# MAX232.net
KiCad netlist of a schematic drawn in Altium Designer
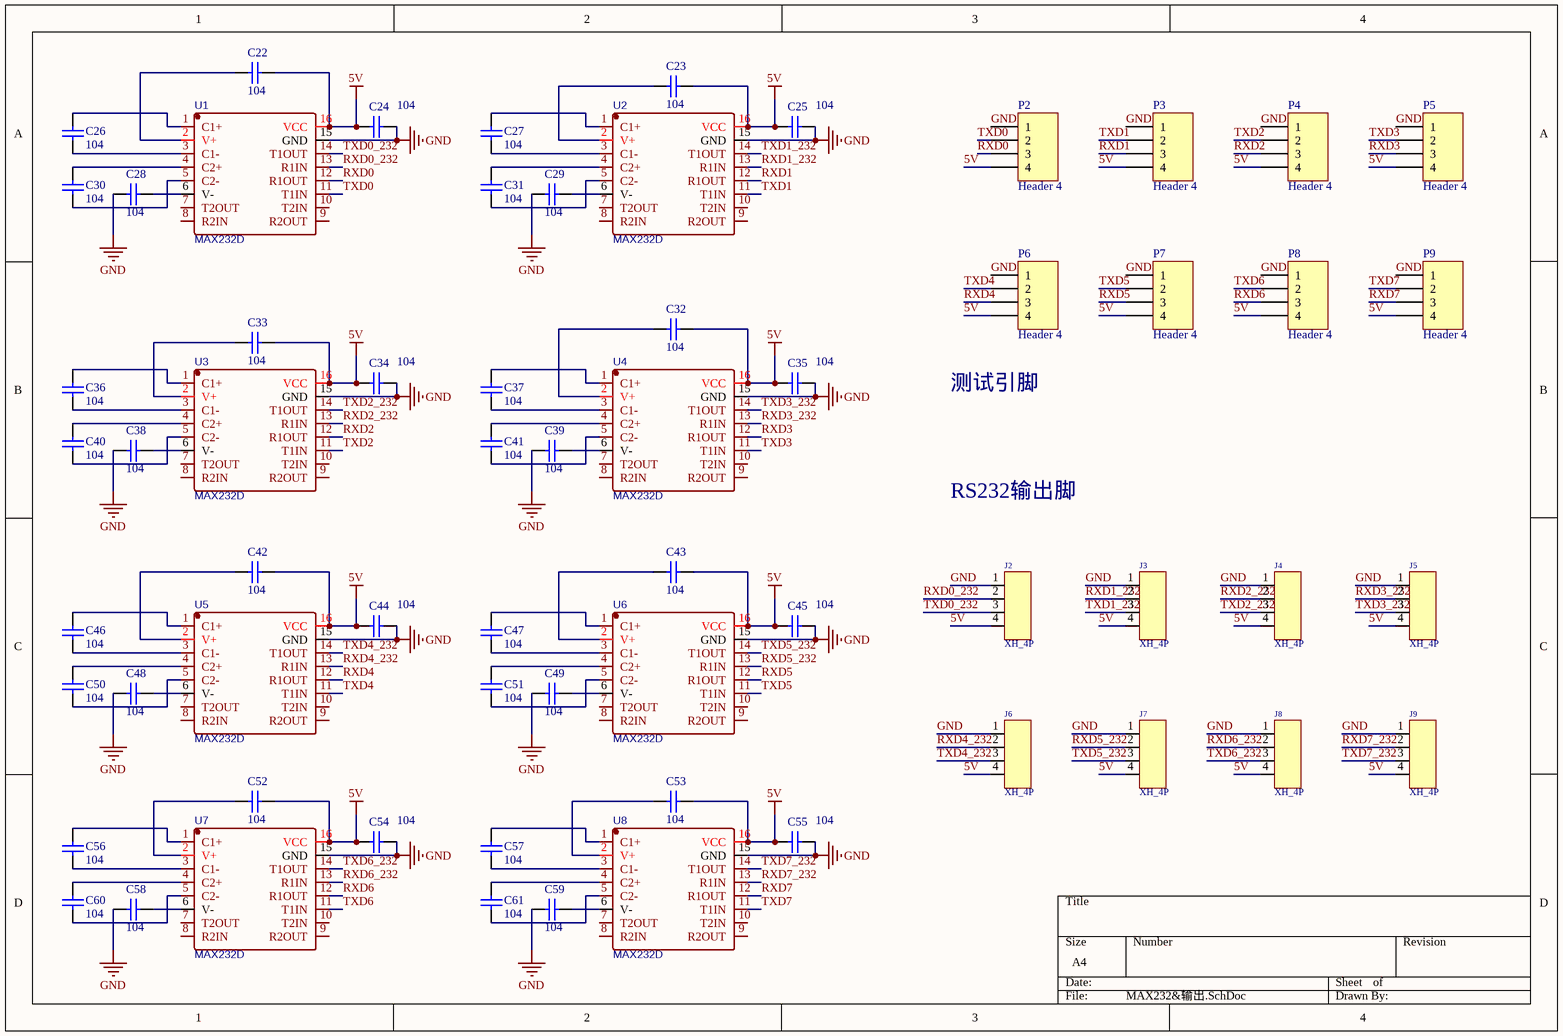
[diagram p0: MAX232&输出.SchDoc]

(export (version "E")
  (design (tool "Eeschema 10.0.6"))
  (components
    (comp (ref "C22")
      (value "104")
      (footprint "0603_C")
      (description "贴片电容")
      (libsource (lib "Miscellaneous Devices LC") (part "0603 100nF (104) 10% 50V"))
    )
    (comp (ref "C23")
      (value "104")
      (footprint "0603_C")
      (description "贴片电容")
      (libsource (lib "Miscellaneous Devices LC") (part "0603 100nF (104) 10% 50V"))
    )
    (comp (ref "C24")
      (value "104")
      (footprint "0603_C")
      (description "贴片电容")
      (libsource (lib "Miscellaneous Devices LC") (part "0603 100nF (104) 10% 50V"))
    )
    (comp (ref "C25")
      (value "104")
      (footprint "0603_C")
      (description "贴片电容")
      (libsource (lib "Miscellaneous Devices LC") (part "0603 100nF (104) 10% 50V"))
    )
    (comp (ref "C26")
      (value "104")
      (footprint "0603_C")
      (description "贴片电容")
      (libsource (lib "Miscellaneous Devices LC") (part "0603 100nF (104) 10% 50V"))
    )
    (comp (ref "C27")
      (value "104")
      (footprint "0603_C")
      (description "贴片电容")
      (libsource (lib "Miscellaneous Devices LC") (part "0603 100nF (104) 10% 50V"))
    )
    (comp (ref "C28")
      (value "104")
      (footprint "0603_C")
      (description "贴片电容")
      (libsource (lib "Miscellaneous Devices LC") (part "0603 100nF (104) 10% 50V"))
    )
    (comp (ref "C29")
      (value "104")
      (footprint "0603_C")
      (description "贴片电容")
      (libsource (lib "Miscellaneous Devices LC") (part "0603 100nF (104) 10% 50V"))
    )
    (comp (ref "C30")
      (value "104")
      (footprint "0603_C")
      (description "贴片电容")
      (libsource (lib "Miscellaneous Devices LC") (part "0603 100nF (104) 10% 50V"))
    )
    (comp (ref "C31")
      (value "104")
      (footprint "0603_C")
      (description "贴片电容")
      (libsource (lib "Miscellaneous Devices LC") (part "0603 100nF (104) 10% 50V"))
    )
    (comp (ref "C32")
      (value "104")
      (footprint "0603_C")
      (description "贴片电容")
      (libsource (lib "Miscellaneous Devices LC") (part "0603 100nF (104) 10% 50V"))
    )
    (comp (ref "C33")
      (value "104")
      (footprint "0603_C")
      (description "贴片电容")
      (libsource (lib "Miscellaneous Devices LC") (part "0603 100nF (104) 10% 50V"))
    )
    (comp (ref "C34")
      (value "104")
      (footprint "0603_C")
      (description "贴片电容")
      (libsource (lib "Miscellaneous Devices LC") (part "0603 100nF (104) 10% 50V"))
    )
    (comp (ref "C35")
      (value "104")
      (footprint "0603_C")
      (description "贴片电容")
      (libsource (lib "Miscellaneous Devices LC") (part "0603 100nF (104) 10% 50V"))
    )
    (comp (ref "C36")
      (value "104")
      (footprint "0603_C")
      (description "贴片电容")
      (libsource (lib "Miscellaneous Devices LC") (part "0603 100nF (104) 10% 50V"))
    )
    (comp (ref "C37")
      (value "104")
      (footprint "0603_C")
      (description "贴片电容")
      (libsource (lib "Miscellaneous Devices LC") (part "0603 100nF (104) 10% 50V"))
    )
    (comp (ref "C38")
      (value "104")
      (footprint "0603_C")
      (description "贴片电容")
      (libsource (lib "Miscellaneous Devices LC") (part "0603 100nF (104) 10% 50V"))
    )
    (comp (ref "C39")
      (value "104")
      (footprint "0603_C")
      (description "贴片电容")
      (libsource (lib "Miscellaneous Devices LC") (part "0603 100nF (104) 10% 50V"))
    )
    (comp (ref "C40")
      (value "104")
      (footprint "0603_C")
      (description "贴片电容")
      (libsource (lib "Miscellaneous Devices LC") (part "0603 100nF (104) 10% 50V"))
    )
    (comp (ref "C41")
      (value "104")
      (footprint "0603_C")
      (description "贴片电容")
      (libsource (lib "Miscellaneous Devices LC") (part "0603 100nF (104) 10% 50V"))
    )
    (comp (ref "C42")
      (value "104")
      (footprint "0603_C")
      (description "贴片电容")
      (libsource (lib "Miscellaneous Devices LC") (part "0603 100nF (104) 10% 50V"))
    )
    (comp (ref "C43")
      (value "104")
      (footprint "0603_C")
      (description "贴片电容")
      (libsource (lib "Miscellaneous Devices LC") (part "0603 100nF (104) 10% 50V"))
    )
    (comp (ref "C44")
      (value "104")
      (footprint "0603_C")
      (description "贴片电容")
      (libsource (lib "Miscellaneous Devices LC") (part "0603 100nF (104) 10% 50V"))
    )
    (comp (ref "C45")
      (value "104")
      (footprint "0603_C")
      (description "贴片电容")
      (libsource (lib "Miscellaneous Devices LC") (part "0603 100nF (104) 10% 50V"))
    )
    (comp (ref "C46")
      (value "104")
      (footprint "0603_C")
      (description "贴片电容")
      (libsource (lib "Miscellaneous Devices LC") (part "0603 100nF (104) 10% 50V"))
    )
    (comp (ref "C47")
      (value "104")
      (footprint "0603_C")
      (description "贴片电容")
      (libsource (lib "Miscellaneous Devices LC") (part "0603 100nF (104) 10% 50V"))
    )
    (comp (ref "C48")
      (value "104")
      (footprint "0603_C")
      (description "贴片电容")
      (libsource (lib "Miscellaneous Devices LC") (part "0603 100nF (104) 10% 50V"))
    )
    (comp (ref "C49")
      (value "104")
      (footprint "0603_C")
      (description "贴片电容")
      (libsource (lib "Miscellaneous Devices LC") (part "0603 100nF (104) 10% 50V"))
    )
    (comp (ref "C50")
      (value "104")
      (footprint "0603_C")
      (description "贴片电容")
      (libsource (lib "Miscellaneous Devices LC") (part "0603 100nF (104) 10% 50V"))
    )
    (comp (ref "C51")
      (value "104")
      (footprint "0603_C")
      (description "贴片电容")
      (libsource (lib "Miscellaneous Devices LC") (part "0603 100nF (104) 10% 50V"))
    )
    (comp (ref "C52")
      (value "104")
      (footprint "0603_C")
      (description "贴片电容")
      (libsource (lib "Miscellaneous Devices LC") (part "0603 100nF (104) 10% 50V"))
    )
    (comp (ref "C53")
      (value "104")
      (footprint "0603_C")
      (description "贴片电容")
      (libsource (lib "Miscellaneous Devices LC") (part "0603 100nF (104) 10% 50V"))
    )
    (comp (ref "C54")
      (value "104")
      (footprint "0603_C")
      (description "贴片电容")
      (libsource (lib "Miscellaneous Devices LC") (part "0603 100nF (104) 10% 50V"))
    )
    (comp (ref "C55")
      (value "104")
      (footprint "0603_C")
      (description "贴片电容")
      (libsource (lib "Miscellaneous Devices LC") (part "0603 100nF (104) 10% 50V"))
    )
    (comp (ref "C56")
      (value "104")
      (footprint "0603_C")
      (description "贴片电容")
      (libsource (lib "Miscellaneous Devices LC") (part "0603 100nF (104) 10% 50V"))
    )
    (comp (ref "C57")
      (value "104")
      (footprint "0603_C")
      (description "贴片电容")
      (libsource (lib "Miscellaneous Devices LC") (part "0603 100nF (104) 10% 50V"))
    )
    (comp (ref "C58")
      (value "104")
      (footprint "0603_C")
      (description "贴片电容")
      (libsource (lib "Miscellaneous Devices LC") (part "0603 100nF (104) 10% 50V"))
    )
    (comp (ref "C59")
      (value "104")
      (footprint "0603_C")
      (description "贴片电容")
      (libsource (lib "Miscellaneous Devices LC") (part "0603 100nF (104) 10% 50V"))
    )
    (comp (ref "C60")
      (value "104")
      (footprint "0603_C")
      (description "贴片电容")
      (libsource (lib "Miscellaneous Devices LC") (part "0603 100nF (104) 10% 50V"))
    )
    (comp (ref "C61")
      (value "104")
      (footprint "0603_C")
      (description "贴片电容")
      (libsource (lib "Miscellaneous Devices LC") (part "0603 100nF (104) 10% 50V"))
    )
    (comp (ref "J2") (value "XH_4P") (footprint "XH_4P直插弯针") (libsource (lib "XH_Connectors") (part "XH_4P")))
    (comp (ref "J3") (value "XH_4P") (footprint "XH_4P直插弯针") (libsource (lib "XH_Connectors") (part "XH_4P")))
    (comp (ref "J4") (value "XH_4P") (footprint "XH_4P直插弯针") (libsource (lib "XH_Connectors") (part "XH_4P")))
    (comp (ref "J5") (value "XH_4P") (footprint "XH_4P直插弯针") (libsource (lib "XH_Connectors") (part "XH_4P")))
    (comp (ref "J6") (value "XH_4P") (footprint "XH_4P直插弯针") (libsource (lib "XH_Connectors") (part "XH_4P")))
    (comp (ref "J7") (value "XH_4P") (footprint "XH_4P直插弯针") (libsource (lib "XH_Connectors") (part "XH_4P")))
    (comp (ref "J8") (value "XH_4P") (footprint "XH_4P直插弯针") (libsource (lib "XH_Connectors") (part "XH_4P")))
    (comp (ref "J9") (value "XH_4P") (footprint "XH_4P直插弯针") (libsource (lib "XH_Connectors") (part "XH_4P")))
    (comp (ref "P2")
      (value "Header 4")
      (footprint "HDR1X4")
      (description "Header, 4-Pin")
      (fields (field (name "PUBLISHER") "Altium Limited"))
      (libsource (lib "Miscellaneous Connectors") (part "Header 4"))
    )
    (comp (ref "P3")
      (value "Header 4")
      (footprint "HDR1X4")
      (description "Header, 4-Pin")
      (fields (field (name "PUBLISHER") "Altium Limited"))
      (libsource (lib "Miscellaneous Connectors") (part "Header 4"))
    )
    (comp (ref "P4")
      (value "Header 4")
      (footprint "HDR1X4")
      (description "Header, 4-Pin")
      (fields (field (name "PUBLISHER") "Altium Limited"))
      (libsource (lib "Miscellaneous Connectors") (part "Header 4"))
    )
    (comp (ref "P5")
      (value "Header 4")
      (footprint "HDR1X4")
      (description "Header, 4-Pin")
      (fields (field (name "PUBLISHER") "Altium Limited"))
      (libsource (lib "Miscellaneous Connectors") (part "Header 4"))
    )
    (comp (ref "P6")
      (value "Header 4")
      (footprint "HDR1X4")
      (description "Header, 4-Pin")
      (fields (field (name "PUBLISHER") "Altium Limited"))
      (libsource (lib "Miscellaneous Connectors") (part "Header 4"))
    )
    (comp (ref "P7")
      (value "Header 4")
      (footprint "HDR1X4")
      (description "Header, 4-Pin")
      (fields (field (name "PUBLISHER") "Altium Limited"))
      (libsource (lib "Miscellaneous Connectors") (part "Header 4"))
    )
    (comp (ref "P8")
      (value "Header 4")
      (footprint "HDR1X4")
      (description "Header, 4-Pin")
      (fields (field (name "PUBLISHER") "Altium Limited"))
      (libsource (lib "Miscellaneous Connectors") (part "Header 4"))
    )
    (comp (ref "P9")
      (value "Header 4")
      (footprint "HDR1X4")
      (description "Header, 4-Pin")
      (fields (field (name "PUBLISHER") "Altium Limited"))
      (libsource (lib "Miscellaneous Connectors") (part "Header 4"))
    )
    (comp (ref "U1")
      (value "MAX232D")
      (footprint "SOIC-16_L9.9-W3.9-P1.27-LS6.0-BL")
      (fields (field (name "BOM_SUPPLIER PART") "C350552") (field (name "CONTRIBUTOR") "LCSC"))
      (libsource (lib "Integrated_Library") (part "MAX232D"))
    )
    (comp (ref "U2")
      (value "MAX232D")
      (footprint "SOIC-16_L9.9-W3.9-P1.27-LS6.0-BL")
      (fields (field (name "BOM_SUPPLIER PART") "C350552") (field (name "CONTRIBUTOR") "LCSC"))
      (libsource (lib "Integrated_Library") (part "MAX232D"))
    )
    (comp (ref "U3")
      (value "MAX232D")
      (footprint "SOIC-16_L9.9-W3.9-P1.27-LS6.0-BL")
      (fields (field (name "BOM_SUPPLIER PART") "C350552") (field (name "CONTRIBUTOR") "LCSC"))
      (libsource (lib "Integrated_Library") (part "MAX232D"))
    )
    (comp (ref "U4")
      (value "MAX232D")
      (footprint "SOIC-16_L9.9-W3.9-P1.27-LS6.0-BL")
      (fields (field (name "BOM_SUPPLIER PART") "C350552") (field (name "CONTRIBUTOR") "LCSC"))
      (libsource (lib "Integrated_Library") (part "MAX232D"))
    )
    (comp (ref "U5")
      (value "MAX232D")
      (footprint "SOIC-16_L9.9-W3.9-P1.27-LS6.0-BL")
      (fields (field (name "BOM_SUPPLIER PART") "C350552") (field (name "CONTRIBUTOR") "LCSC"))
      (libsource (lib "Integrated_Library") (part "MAX232D"))
    )
    (comp (ref "U6")
      (value "MAX232D")
      (footprint "SOIC-16_L9.9-W3.9-P1.27-LS6.0-BL")
      (fields (field (name "BOM_SUPPLIER PART") "C350552") (field (name "CONTRIBUTOR") "LCSC"))
      (libsource (lib "Integrated_Library") (part "MAX232D"))
    )
    (comp (ref "U7")
      (value "MAX232D")
      (footprint "SOIC-16_L9.9-W3.9-P1.27-LS6.0-BL")
      (fields (field (name "BOM_SUPPLIER PART") "C350552") (field (name "CONTRIBUTOR") "LCSC"))
      (libsource (lib "Integrated_Library") (part "MAX232D"))
    )
    (comp (ref "U8")
      (value "MAX232D")
      (footprint "SOIC-16_L9.9-W3.9-P1.27-LS6.0-BL")
      (fields (field (name "BOM_SUPPLIER PART") "C350552") (field (name "CONTRIBUTOR") "LCSC"))
      (libsource (lib "Integrated_Library") (part "MAX232D"))
    )
  )
  (nets
    (net (code "1") (name "/RXD0") (class "Default")
      (node (ref "P2") (pin "3") (pinfunction "3_3") (pintype "passive"))
      (node (ref "U1") (pin "12") (pinfunction "R1OUT_12") (pintype "passive"))
    )
    (net (code "2") (name "/RXD0_232") (class "Default")
      (node (ref "J2") (pin "2") (pinfunction "2_2") (pintype "passive"))
      (node (ref "U1") (pin "13") (pinfunction "R1IN_13") (pintype "passive"))
    )
    (net (code "3") (name "/RXD1") (class "Default")
      (node (ref "P3") (pin "3") (pinfunction "3_3") (pintype "passive"))
      (node (ref "U2") (pin "12") (pinfunction "R1OUT_12") (pintype "passive"))
    )
    (net (code "4") (name "/RXD1_232") (class "Default")
      (node (ref "J3") (pin "2") (pinfunction "2_2") (pintype "passive"))
      (node (ref "U2") (pin "13") (pinfunction "R1IN_13") (pintype "passive"))
    )
    (net (code "5") (name "/RXD2") (class "Default")
      (node (ref "P4") (pin "3") (pinfunction "3_3") (pintype "passive"))
      (node (ref "U3") (pin "12") (pinfunction "R1OUT_12") (pintype "passive"))
    )
    (net (code "6") (name "/RXD2_232") (class "Default")
      (node (ref "J4") (pin "2") (pinfunction "2_2") (pintype "passive"))
      (node (ref "U3") (pin "13") (pinfunction "R1IN_13") (pintype "passive"))
    )
    (net (code "7") (name "/RXD3") (class "Default")
      (node (ref "P5") (pin "3") (pinfunction "3_3") (pintype "passive"))
      (node (ref "U4") (pin "12") (pinfunction "R1OUT_12") (pintype "passive"))
    )
    (net (code "8") (name "/RXD3_232") (class "Default")
      (node (ref "J5") (pin "2") (pinfunction "2_2") (pintype "passive"))
      (node (ref "U4") (pin "13") (pinfunction "R1IN_13") (pintype "passive"))
    )
    (net (code "9") (name "/RXD4") (class "Default")
      (node (ref "P6") (pin "3") (pinfunction "3_3") (pintype "passive"))
      (node (ref "U5") (pin "12") (pinfunction "R1OUT_12") (pintype "passive"))
    )
    (net (code "10") (name "/RXD4_232") (class "Default")
      (node (ref "J6") (pin "2") (pinfunction "2_2") (pintype "passive"))
      (node (ref "U5") (pin "13") (pinfunction "R1IN_13") (pintype "passive"))
    )
    (net (code "11") (name "/RXD5") (class "Default")
      (node (ref "P7") (pin "3") (pinfunction "3_3") (pintype "passive"))
      (node (ref "U6") (pin "12") (pinfunction "R1OUT_12") (pintype "passive"))
    )
    (net (code "12") (name "/RXD5_232") (class "Default")
      (node (ref "J7") (pin "2") (pinfunction "2_2") (pintype "passive"))
      (node (ref "U6") (pin "13") (pinfunction "R1IN_13") (pintype "passive"))
    )
    (net (code "13") (name "/RXD6") (class "Default")
      (node (ref "P8") (pin "3") (pinfunction "3_3") (pintype "passive"))
      (node (ref "U7") (pin "12") (pinfunction "R1OUT_12") (pintype "passive"))
    )
    (net (code "14") (name "/RXD6_232") (class "Default")
      (node (ref "J8") (pin "2") (pinfunction "2_2") (pintype "passive"))
      (node (ref "U7") (pin "13") (pinfunction "R1IN_13") (pintype "passive"))
    )
    (net (code "15") (name "/RXD7") (class "Default")
      (node (ref "P9") (pin "3") (pinfunction "3_3") (pintype "passive"))
      (node (ref "U8") (pin "12") (pinfunction "R1OUT_12") (pintype "passive"))
    )
    (net (code "16") (name "/RXD7_232") (class "Default")
      (node (ref "J9") (pin "2") (pinfunction "2_2") (pintype "passive"))
      (node (ref "U8") (pin "13") (pinfunction "R1IN_13") (pintype "passive"))
    )
    (net (code "17") (name "/TXD0") (class "Default")
      (node (ref "P2") (pin "2") (pinfunction "2_2") (pintype "passive"))
      (node (ref "U1") (pin "11") (pinfunction "T1IN_11") (pintype "passive"))
    )
    (net (code "18") (name "/TXD0_232") (class "Default")
      (node (ref "J2") (pin "3") (pinfunction "3_3") (pintype "passive"))
      (node (ref "U1") (pin "14") (pinfunction "T1OUT_14") (pintype "passive"))
    )
    (net (code "19") (name "/TXD1") (class "Default")
      (node (ref "P3") (pin "2") (pinfunction "2_2") (pintype "passive"))
      (node (ref "U2") (pin "11") (pinfunction "T1IN_11") (pintype "passive"))
    )
    (net (code "20") (name "/TXD1_232") (class "Default")
      (node (ref "J3") (pin "3") (pinfunction "3_3") (pintype "passive"))
      (node (ref "U2") (pin "14") (pinfunction "T1OUT_14") (pintype "passive"))
    )
    (net (code "21") (name "/TXD2") (class "Default")
      (node (ref "P4") (pin "2") (pinfunction "2_2") (pintype "passive"))
      (node (ref "U3") (pin "11") (pinfunction "T1IN_11") (pintype "passive"))
    )
    (net (code "22") (name "/TXD2_232") (class "Default")
      (node (ref "J4") (pin "3") (pinfunction "3_3") (pintype "passive"))
      (node (ref "U3") (pin "14") (pinfunction "T1OUT_14") (pintype "passive"))
    )
    (net (code "23") (name "/TXD3") (class "Default")
      (node (ref "P5") (pin "2") (pinfunction "2_2") (pintype "passive"))
      (node (ref "U4") (pin "11") (pinfunction "T1IN_11") (pintype "passive"))
    )
    (net (code "24") (name "/TXD3_232") (class "Default")
      (node (ref "J5") (pin "3") (pinfunction "3_3") (pintype "passive"))
      (node (ref "U4") (pin "14") (pinfunction "T1OUT_14") (pintype "passive"))
    )
    (net (code "25") (name "/TXD4") (class "Default")
      (node (ref "P6") (pin "2") (pinfunction "2_2") (pintype "passive"))
      (node (ref "U5") (pin "11") (pinfunction "T1IN_11") (pintype "passive"))
    )
    (net (code "26") (name "/TXD4_232") (class "Default")
      (node (ref "J6") (pin "3") (pinfunction "3_3") (pintype "passive"))
      (node (ref "U5") (pin "14") (pinfunction "T1OUT_14") (pintype "passive"))
    )
    (net (code "27") (name "/TXD5") (class "Default")
      (node (ref "P7") (pin "2") (pinfunction "2_2") (pintype "passive"))
      (node (ref "U6") (pin "11") (pinfunction "T1IN_11") (pintype "passive"))
    )
    (net (code "28") (name "/TXD5_232") (class "Default")
      (node (ref "J7") (pin "3") (pinfunction "3_3") (pintype "passive"))
      (node (ref "U6") (pin "14") (pinfunction "T1OUT_14") (pintype "passive"))
    )
    (net (code "29") (name "/TXD6") (class "Default")
      (node (ref "P8") (pin "2") (pinfunction "2_2") (pintype "passive"))
      (node (ref "U7") (pin "11") (pinfunction "T1IN_11") (pintype "passive"))
    )
    (net (code "30") (name "/TXD6_232") (class "Default")
      (node (ref "J8") (pin "3") (pinfunction "3_3") (pintype "passive"))
      (node (ref "U7") (pin "14") (pinfunction "T1OUT_14") (pintype "passive"))
    )
    (net (code "31") (name "/TXD7") (class "Default")
      (node (ref "P9") (pin "2") (pinfunction "2_2") (pintype "passive"))
      (node (ref "U8") (pin "11") (pinfunction "T1IN_11") (pintype "passive"))
    )
    (net (code "32") (name "/TXD7_232") (class "Default")
      (node (ref "J9") (pin "3") (pinfunction "3_3") (pintype "passive"))
      (node (ref "U8") (pin "14") (pinfunction "T1OUT_14") (pintype "passive"))
    )
    (net (code "33") (name "5V") (class "Default")
      (node (ref "C22") (pin "1") (pinfunction "1_1") (pintype "passive"))
      (node (ref "C23") (pin "1") (pinfunction "1_1") (pintype "passive"))
      (node (ref "C24") (pin "1") (pinfunction "1_1") (pintype "passive"))
      (node (ref "C25") (pin "1") (pinfunction "1_1") (pintype "passive"))
      (node (ref "C32") (pin "1") (pinfunction "1_1") (pintype "passive"))
      (node (ref "C33") (pin "1") (pinfunction "1_1") (pintype "passive"))
      (node (ref "C34") (pin "1") (pinfunction "1_1") (pintype "passive"))
      (node (ref "C35") (pin "1") (pinfunction "1_1") (pintype "passive"))
      (node (ref "C42") (pin "1") (pinfunction "1_1") (pintype "passive"))
      (node (ref "C43") (pin "1") (pinfunction "1_1") (pintype "passive"))
      (node (ref "C44") (pin "1") (pinfunction "1_1") (pintype "passive"))
      (node (ref "C45") (pin "1") (pinfunction "1_1") (pintype "passive"))
      (node (ref "C52") (pin "1") (pinfunction "1_1") (pintype "passive"))
      (node (ref "C53") (pin "1") (pinfunction "1_1") (pintype "passive"))
      (node (ref "C54") (pin "1") (pinfunction "1_1") (pintype "passive"))
      (node (ref "C55") (pin "1") (pinfunction "1_1") (pintype "passive"))
      (node (ref "J2") (pin "4") (pinfunction "4_4") (pintype "passive"))
      (node (ref "J3") (pin "4") (pinfunction "4_4") (pintype "passive"))
      (node (ref "J4") (pin "4") (pinfunction "4_4") (pintype "passive"))
      (node (ref "J5") (pin "4") (pinfunction "4_4") (pintype "passive"))
      (node (ref "J6") (pin "4") (pinfunction "4_4") (pintype "passive"))
      (node (ref "J7") (pin "4") (pinfunction "4_4") (pintype "passive"))
      (node (ref "J8") (pin "4") (pinfunction "4_4") (pintype "passive"))
      (node (ref "J9") (pin "4") (pinfunction "4_4") (pintype "passive"))
      (node (ref "P2") (pin "4") (pinfunction "4_4") (pintype "passive"))
      (node (ref "P3") (pin "4") (pinfunction "4_4") (pintype "passive"))
      (node (ref "P4") (pin "4") (pinfunction "4_4") (pintype "passive"))
      (node (ref "P5") (pin "4") (pinfunction "4_4") (pintype "passive"))
      (node (ref "P6") (pin "4") (pinfunction "4_4") (pintype "passive"))
      (node (ref "P7") (pin "4") (pinfunction "4_4") (pintype "passive"))
      (node (ref "P8") (pin "4") (pinfunction "4_4") (pintype "passive"))
      (node (ref "P9") (pin "4") (pinfunction "4_4") (pintype "passive"))
      (node (ref "U1") (pin "16") (pinfunction "VCC_16") (pintype "passive"))
      (node (ref "U2") (pin "16") (pinfunction "VCC_16") (pintype "passive"))
      (node (ref "U3") (pin "16") (pinfunction "VCC_16") (pintype "passive"))
      (node (ref "U4") (pin "16") (pinfunction "VCC_16") (pintype "passive"))
      (node (ref "U5") (pin "16") (pinfunction "VCC_16") (pintype "passive"))
      (node (ref "U6") (pin "16") (pinfunction "VCC_16") (pintype "passive"))
      (node (ref "U7") (pin "16") (pinfunction "VCC_16") (pintype "passive"))
      (node (ref "U8") (pin "16") (pinfunction "VCC_16") (pintype "passive"))
    )
    (net (code "34") (name "GND") (class "Default")
      (node (ref "C24") (pin "2") (pinfunction "2_2") (pintype "passive"))
      (node (ref "C25") (pin "2") (pinfunction "2_2") (pintype "passive"))
      (node (ref "C28") (pin "1") (pinfunction "1_1") (pintype "passive"))
      (node (ref "C29") (pin "1") (pinfunction "1_1") (pintype "passive"))
      (node (ref "C34") (pin "2") (pinfunction "2_2") (pintype "passive"))
      (node (ref "C35") (pin "2") (pinfunction "2_2") (pintype "passive"))
      (node (ref "C38") (pin "1") (pinfunction "1_1") (pintype "passive"))
      (node (ref "C39") (pin "1") (pinfunction "1_1") (pintype "passive"))
      (node (ref "C44") (pin "2") (pinfunction "2_2") (pintype "passive"))
      (node (ref "C45") (pin "2") (pinfunction "2_2") (pintype "passive"))
      (node (ref "C48") (pin "1") (pinfunction "1_1") (pintype "passive"))
      (node (ref "C49") (pin "1") (pinfunction "1_1") (pintype "passive"))
      (node (ref "C54") (pin "2") (pinfunction "2_2") (pintype "passive"))
      (node (ref "C55") (pin "2") (pinfunction "2_2") (pintype "passive"))
      (node (ref "C58") (pin "1") (pinfunction "1_1") (pintype "passive"))
      (node (ref "C59") (pin "1") (pinfunction "1_1") (pintype "passive"))
      (node (ref "J2") (pin "1") (pinfunction "1_1") (pintype "passive"))
      (node (ref "J3") (pin "1") (pinfunction "1_1") (pintype "passive"))
      (node (ref "J4") (pin "1") (pinfunction "1_1") (pintype "passive"))
      (node (ref "J5") (pin "1") (pinfunction "1_1") (pintype "passive"))
      (node (ref "J6") (pin "1") (pinfunction "1_1") (pintype "passive"))
      (node (ref "J7") (pin "1") (pinfunction "1_1") (pintype "passive"))
      (node (ref "J8") (pin "1") (pinfunction "1_1") (pintype "passive"))
      (node (ref "J9") (pin "1") (pinfunction "1_1") (pintype "passive"))
      (node (ref "P2") (pin "1") (pinfunction "1_1") (pintype "passive"))
      (node (ref "P3") (pin "1") (pinfunction "1_1") (pintype "passive"))
      (node (ref "P4") (pin "1") (pinfunction "1_1") (pintype "passive"))
      (node (ref "P5") (pin "1") (pinfunction "1_1") (pintype "passive"))
      (node (ref "P6") (pin "1") (pinfunction "1_1") (pintype "passive"))
      (node (ref "P7") (pin "1") (pinfunction "1_1") (pintype "passive"))
      (node (ref "P8") (pin "1") (pinfunction "1_1") (pintype "passive"))
      (node (ref "P9") (pin "1") (pinfunction "1_1") (pintype "passive"))
      (node (ref "U1") (pin "15") (pinfunction "GND_15") (pintype "passive"))
      (node (ref "U2") (pin "15") (pinfunction "GND_15") (pintype "passive"))
      (node (ref "U3") (pin "15") (pinfunction "GND_15") (pintype "passive"))
      (node (ref "U4") (pin "15") (pinfunction "GND_15") (pintype "passive"))
      (node (ref "U5") (pin "15") (pinfunction "GND_15") (pintype "passive"))
      (node (ref "U6") (pin "15") (pinfunction "GND_15") (pintype "passive"))
      (node (ref "U7") (pin "15") (pinfunction "GND_15") (pintype "passive"))
      (node (ref "U8") (pin "15") (pinfunction "GND_15") (pintype "passive"))
    )
    (net (code "35") (name "Net-(U1-C1+)") (class "Default")
      (node (ref "C26") (pin "2") (pinfunction "2_2") (pintype "passive"))
      (node (ref "U1") (pin "1") (pinfunction "C1+_1") (pintype "passive"))
    )
    (net (code "36") (name "Net-(U1-C1-)") (class "Default")
      (node (ref "C26") (pin "1") (pinfunction "1_1") (pintype "passive"))
      (node (ref "U1") (pin "3") (pinfunction "C1-_3") (pintype "passive"))
    )
    (net (code "37") (name "Net-(U1-C2+)") (class "Default")
      (node (ref "C30") (pin "2") (pinfunction "2_2") (pintype "passive"))
      (node (ref "U1") (pin "4") (pinfunction "C2+_4") (pintype "passive"))
    )
    (net (code "38") (name "Net-(U1-C2-)") (class "Default")
      (node (ref "C30") (pin "1") (pinfunction "1_1") (pintype "passive"))
      (node (ref "U1") (pin "5") (pinfunction "C2-_5") (pintype "passive"))
    )
    (net (code "39") (name "Net-(U1-V+)") (class "Default")
      (node (ref "C22") (pin "2") (pinfunction "2_2") (pintype "passive"))
      (node (ref "U1") (pin "2") (pinfunction "V+_2") (pintype "passive"))
    )
    (net (code "40") (name "Net-(U1-V-)") (class "Default")
      (node (ref "C28") (pin "2") (pinfunction "2_2") (pintype "passive"))
      (node (ref "U1") (pin "6") (pinfunction "V-_6") (pintype "passive"))
    )
    (net (code "41") (name "Net-(U2-C1+)") (class "Default")
      (node (ref "C27") (pin "2") (pinfunction "2_2") (pintype "passive"))
      (node (ref "U2") (pin "1") (pinfunction "C1+_1") (pintype "passive"))
    )
    (net (code "42") (name "Net-(U2-C1-)") (class "Default")
      (node (ref "C27") (pin "1") (pinfunction "1_1") (pintype "passive"))
      (node (ref "U2") (pin "3") (pinfunction "C1-_3") (pintype "passive"))
    )
    (net (code "43") (name "Net-(U2-C2+)") (class "Default")
      (node (ref "C31") (pin "2") (pinfunction "2_2") (pintype "passive"))
      (node (ref "U2") (pin "4") (pinfunction "C2+_4") (pintype "passive"))
    )
    (net (code "44") (name "Net-(U2-C2-)") (class "Default")
      (node (ref "C31") (pin "1") (pinfunction "1_1") (pintype "passive"))
      (node (ref "U2") (pin "5") (pinfunction "C2-_5") (pintype "passive"))
    )
    (net (code "45") (name "Net-(U2-V+)") (class "Default")
      (node (ref "C23") (pin "2") (pinfunction "2_2") (pintype "passive"))
      (node (ref "U2") (pin "2") (pinfunction "V+_2") (pintype "passive"))
    )
    (net (code "46") (name "Net-(U2-V-)") (class "Default")
      (node (ref "C29") (pin "2") (pinfunction "2_2") (pintype "passive"))
      (node (ref "U2") (pin "6") (pinfunction "V-_6") (pintype "passive"))
    )
    (net (code "47") (name "Net-(U3-C1+)") (class "Default")
      (node (ref "C36") (pin "2") (pinfunction "2_2") (pintype "passive"))
      (node (ref "U3") (pin "1") (pinfunction "C1+_1") (pintype "passive"))
    )
    (net (code "48") (name "Net-(U3-C1-)") (class "Default")
      (node (ref "C36") (pin "1") (pinfunction "1_1") (pintype "passive"))
      (node (ref "U3") (pin "3") (pinfunction "C1-_3") (pintype "passive"))
    )
    (net (code "49") (name "Net-(U3-C2+)") (class "Default")
      (node (ref "C40") (pin "2") (pinfunction "2_2") (pintype "passive"))
      (node (ref "U3") (pin "4") (pinfunction "C2+_4") (pintype "passive"))
    )
    (net (code "50") (name "Net-(U3-C2-)") (class "Default")
      (node (ref "C40") (pin "1") (pinfunction "1_1") (pintype "passive"))
      (node (ref "U3") (pin "5") (pinfunction "C2-_5") (pintype "passive"))
    )
    (net (code "51") (name "Net-(U3-V+)") (class "Default")
      (node (ref "C33") (pin "2") (pinfunction "2_2") (pintype "passive"))
      (node (ref "U3") (pin "2") (pinfunction "V+_2") (pintype "passive"))
    )
    (net (code "52") (name "Net-(U3-V-)") (class "Default")
      (node (ref "C38") (pin "2") (pinfunction "2_2") (pintype "passive"))
      (node (ref "U3") (pin "6") (pinfunction "V-_6") (pintype "passive"))
    )
    (net (code "53") (name "Net-(U4-C1+)") (class "Default")
      (node (ref "C37") (pin "2") (pinfunction "2_2") (pintype "passive"))
      (node (ref "U4") (pin "1") (pinfunction "C1+_1") (pintype "passive"))
    )
    (net (code "54") (name "Net-(U4-C1-)") (class "Default")
      (node (ref "C37") (pin "1") (pinfunction "1_1") (pintype "passive"))
      (node (ref "U4") (pin "3") (pinfunction "C1-_3") (pintype "passive"))
    )
    (net (code "55") (name "Net-(U4-C2+)") (class "Default")
      (node (ref "C41") (pin "2") (pinfunction "2_2") (pintype "passive"))
      (node (ref "U4") (pin "4") (pinfunction "C2+_4") (pintype "passive"))
    )
    (net (code "56") (name "Net-(U4-C2-)") (class "Default")
      (node (ref "C41") (pin "1") (pinfunction "1_1") (pintype "passive"))
      (node (ref "U4") (pin "5") (pinfunction "C2-_5") (pintype "passive"))
    )
    (net (code "57") (name "Net-(U4-V+)") (class "Default")
      (node (ref "C32") (pin "2") (pinfunction "2_2") (pintype "passive"))
      (node (ref "U4") (pin "2") (pinfunction "V+_2") (pintype "passive"))
    )
    (net (code "58") (name "Net-(U4-V-)") (class "Default")
      (node (ref "C39") (pin "2") (pinfunction "2_2") (pintype "passive"))
      (node (ref "U4") (pin "6") (pinfunction "V-_6") (pintype "passive"))
    )
    (net (code "59") (name "Net-(U5-C1+)") (class "Default")
      (node (ref "C46") (pin "2") (pinfunction "2_2") (pintype "passive"))
      (node (ref "U5") (pin "1") (pinfunction "C1+_1") (pintype "passive"))
    )
    (net (code "60") (name "Net-(U5-C1-)") (class "Default")
      (node (ref "C46") (pin "1") (pinfunction "1_1") (pintype "passive"))
      (node (ref "U5") (pin "3") (pinfunction "C1-_3") (pintype "passive"))
    )
    (net (code "61") (name "Net-(U5-C2+)") (class "Default")
      (node (ref "C50") (pin "2") (pinfunction "2_2") (pintype "passive"))
      (node (ref "U5") (pin "4") (pinfunction "C2+_4") (pintype "passive"))
    )
    (net (code "62") (name "Net-(U5-C2-)") (class "Default")
      (node (ref "C50") (pin "1") (pinfunction "1_1") (pintype "passive"))
      (node (ref "U5") (pin "5") (pinfunction "C2-_5") (pintype "passive"))
    )
    (net (code "63") (name "Net-(U5-V+)") (class "Default")
      (node (ref "C42") (pin "2") (pinfunction "2_2") (pintype "passive"))
      (node (ref "U5") (pin "2") (pinfunction "V+_2") (pintype "passive"))
    )
    (net (code "64") (name "Net-(U5-V-)") (class "Default")
      (node (ref "C48") (pin "2") (pinfunction "2_2") (pintype "passive"))
      (node (ref "U5") (pin "6") (pinfunction "V-_6") (pintype "passive"))
    )
    (net (code "65") (name "Net-(U6-C1+)") (class "Default")
      (node (ref "C47") (pin "2") (pinfunction "2_2") (pintype "passive"))
      (node (ref "U6") (pin "1") (pinfunction "C1+_1") (pintype "passive"))
    )
    (net (code "66") (name "Net-(U6-C1-)") (class "Default")
      (node (ref "C47") (pin "1") (pinfunction "1_1") (pintype "passive"))
      (node (ref "U6") (pin "3") (pinfunction "C1-_3") (pintype "passive"))
    )
    (net (code "67") (name "Net-(U6-C2+)") (class "Default")
      (node (ref "C51") (pin "2") (pinfunction "2_2") (pintype "passive"))
      (node (ref "U6") (pin "4") (pinfunction "C2+_4") (pintype "passive"))
    )
    (net (code "68") (name "Net-(U6-C2-)") (class "Default")
      (node (ref "C51") (pin "1") (pinfunction "1_1") (pintype "passive"))
      (node (ref "U6") (pin "5") (pinfunction "C2-_5") (pintype "passive"))
    )
    (net (code "69") (name "Net-(U6-V+)") (class "Default")
      (node (ref "C43") (pin "2") (pinfunction "2_2") (pintype "passive"))
      (node (ref "U6") (pin "2") (pinfunction "V+_2") (pintype "passive"))
    )
    (net (code "70") (name "Net-(U6-V-)") (class "Default")
      (node (ref "C49") (pin "2") (pinfunction "2_2") (pintype "passive"))
      (node (ref "U6") (pin "6") (pinfunction "V-_6") (pintype "passive"))
    )
    (net (code "71") (name "Net-(U7-C1+)") (class "Default")
      (node (ref "C56") (pin "2") (pinfunction "2_2") (pintype "passive"))
      (node (ref "U7") (pin "1") (pinfunction "C1+_1") (pintype "passive"))
    )
    (net (code "72") (name "Net-(U7-C1-)") (class "Default")
      (node (ref "C56") (pin "1") (pinfunction "1_1") (pintype "passive"))
      (node (ref "U7") (pin "3") (pinfunction "C1-_3") (pintype "passive"))
    )
    (net (code "73") (name "Net-(U7-C2+)") (class "Default")
      (node (ref "C60") (pin "2") (pinfunction "2_2") (pintype "passive"))
      (node (ref "U7") (pin "4") (pinfunction "C2+_4") (pintype "passive"))
    )
    (net (code "74") (name "Net-(U7-C2-)") (class "Default")
      (node (ref "C60") (pin "1") (pinfunction "1_1") (pintype "passive"))
      (node (ref "U7") (pin "5") (pinfunction "C2-_5") (pintype "passive"))
    )
    (net (code "75") (name "Net-(U7-V+)") (class "Default")
      (node (ref "C52") (pin "2") (pinfunction "2_2") (pintype "passive"))
      (node (ref "U7") (pin "2") (pinfunction "V+_2") (pintype "passive"))
    )
    (net (code "76") (name "Net-(U7-V-)") (class "Default")
      (node (ref "C58") (pin "2") (pinfunction "2_2") (pintype "passive"))
      (node (ref "U7") (pin "6") (pinfunction "V-_6") (pintype "passive"))
    )
    (net (code "77") (name "Net-(U8-C1+)") (class "Default")
      (node (ref "C57") (pin "2") (pinfunction "2_2") (pintype "passive"))
      (node (ref "U8") (pin "1") (pinfunction "C1+_1") (pintype "passive"))
    )
    (net (code "78") (name "Net-(U8-C1-)") (class "Default")
      (node (ref "C57") (pin "1") (pinfunction "1_1") (pintype "passive"))
      (node (ref "U8") (pin "3") (pinfunction "C1-_3") (pintype "passive"))
    )
    (net (code "79") (name "Net-(U8-C2+)") (class "Default")
      (node (ref "C61") (pin "2") (pinfunction "2_2") (pintype "passive"))
      (node (ref "U8") (pin "4") (pinfunction "C2+_4") (pintype "passive"))
    )
    (net (code "80") (name "Net-(U8-C2-)") (class "Default")
      (node (ref "C61") (pin "1") (pinfunction "1_1") (pintype "passive"))
      (node (ref "U8") (pin "5") (pinfunction "C2-_5") (pintype "passive"))
    )
    (net (code "81") (name "Net-(U8-V+)") (class "Default")
      (node (ref "C53") (pin "2") (pinfunction "2_2") (pintype "passive"))
      (node (ref "U8") (pin "2") (pinfunction "V+_2") (pintype "passive"))
    )
    (net (code "82") (name "Net-(U8-V-)") (class "Default")
      (node (ref "C59") (pin "2") (pinfunction "2_2") (pintype "passive"))
      (node (ref "U8") (pin "6") (pinfunction "V-_6") (pintype "passive"))
    )
    (net (code "83") (name "unconnected-(U1-R2IN-Pad8)") (class "Default")
      (node (ref "U1") (pin "8") (pinfunction "R2IN_8") (pintype "passive"))
    )
    (net (code "84") (name "unconnected-(U1-R2OUT-Pad9)") (class "Default")
      (node (ref "U1") (pin "9") (pinfunction "R2OUT_9") (pintype "passive"))
    )
    (net (code "85") (name "unconnected-(U1-T2IN-Pad10)") (class "Default")
      (node (ref "U1") (pin "10") (pinfunction "T2IN_10") (pintype "passive"))
    )
    (net (code "86") (name "unconnected-(U1-T2OUT-Pad7)") (class "Default")
      (node (ref "U1") (pin "7") (pinfunction "T2OUT_7") (pintype "passive"))
    )
    (net (code "87") (name "unconnected-(U2-R2IN-Pad8)") (class "Default")
      (node (ref "U2") (pin "8") (pinfunction "R2IN_8") (pintype "passive"))
    )
    (net (code "88") (name "unconnected-(U2-R2OUT-Pad9)") (class "Default")
      (node (ref "U2") (pin "9") (pinfunction "R2OUT_9") (pintype "passive"))
    )
    (net (code "89") (name "unconnected-(U2-T2IN-Pad10)") (class "Default")
      (node (ref "U2") (pin "10") (pinfunction "T2IN_10") (pintype "passive"))
    )
    (net (code "90") (name "unconnected-(U2-T2OUT-Pad7)") (class "Default")
      (node (ref "U2") (pin "7") (pinfunction "T2OUT_7") (pintype "passive"))
    )
    (net (code "91") (name "unconnected-(U3-R2IN-Pad8)") (class "Default")
      (node (ref "U3") (pin "8") (pinfunction "R2IN_8") (pintype "passive"))
    )
    (net (code "92") (name "unconnected-(U3-R2OUT-Pad9)") (class "Default")
      (node (ref "U3") (pin "9") (pinfunction "R2OUT_9") (pintype "passive"))
    )
    (net (code "93") (name "unconnected-(U3-T2IN-Pad10)") (class "Default")
      (node (ref "U3") (pin "10") (pinfunction "T2IN_10") (pintype "passive"))
    )
    (net (code "94") (name "unconnected-(U3-T2OUT-Pad7)") (class "Default")
      (node (ref "U3") (pin "7") (pinfunction "T2OUT_7") (pintype "passive"))
    )
    (net (code "95") (name "unconnected-(U4-R2IN-Pad8)") (class "Default")
      (node (ref "U4") (pin "8") (pinfunction "R2IN_8") (pintype "passive"))
    )
    (net (code "96") (name "unconnected-(U4-R2OUT-Pad9)") (class "Default")
      (node (ref "U4") (pin "9") (pinfunction "R2OUT_9") (pintype "passive"))
    )
    (net (code "97") (name "unconnected-(U4-T2IN-Pad10)") (class "Default")
      (node (ref "U4") (pin "10") (pinfunction "T2IN_10") (pintype "passive"))
    )
    (net (code "98") (name "unconnected-(U4-T2OUT-Pad7)") (class "Default")
      (node (ref "U4") (pin "7") (pinfunction "T2OUT_7") (pintype "passive"))
    )
    (net (code "99") (name "unconnected-(U5-R2IN-Pad8)") (class "Default")
      (node (ref "U5") (pin "8") (pinfunction "R2IN_8") (pintype "passive"))
    )
    (net (code "100") (name "unconnected-(U5-R2OUT-Pad9)") (class "Default")
      (node (ref "U5") (pin "9") (pinfunction "R2OUT_9") (pintype "passive"))
    )
    (net (code "101") (name "unconnected-(U5-T2IN-Pad10)") (class "Default")
      (node (ref "U5") (pin "10") (pinfunction "T2IN_10") (pintype "passive"))
    )
    (net (code "102") (name "unconnected-(U5-T2OUT-Pad7)") (class "Default")
      (node (ref "U5") (pin "7") (pinfunction "T2OUT_7") (pintype "passive"))
    )
    (net (code "103") (name "unconnected-(U6-R2IN-Pad8)") (class "Default")
      (node (ref "U6") (pin "8") (pinfunction "R2IN_8") (pintype "passive"))
    )
    (net (code "104") (name "unconnected-(U6-R2OUT-Pad9)") (class "Default")
      (node (ref "U6") (pin "9") (pinfunction "R2OUT_9") (pintype "passive"))
    )
    (net (code "105") (name "unconnected-(U6-T2IN-Pad10)") (class "Default")
      (node (ref "U6") (pin "10") (pinfunction "T2IN_10") (pintype "passive"))
    )
    (net (code "106") (name "unconnected-(U6-T2OUT-Pad7)") (class "Default")
      (node (ref "U6") (pin "7") (pinfunction "T2OUT_7") (pintype "passive"))
    )
    (net (code "107") (name "unconnected-(U7-R2IN-Pad8)") (class "Default")
      (node (ref "U7") (pin "8") (pinfunction "R2IN_8") (pintype "passive"))
    )
    (net (code "108") (name "unconnected-(U7-R2OUT-Pad9)") (class "Default")
      (node (ref "U7") (pin "9") (pinfunction "R2OUT_9") (pintype "passive"))
    )
    (net (code "109") (name "unconnected-(U7-T2IN-Pad10)") (class "Default")
      (node (ref "U7") (pin "10") (pinfunction "T2IN_10") (pintype "passive"))
    )
    (net (code "110") (name "unconnected-(U7-T2OUT-Pad7)") (class "Default")
      (node (ref "U7") (pin "7") (pinfunction "T2OUT_7") (pintype "passive"))
    )
    (net (code "111") (name "unconnected-(U8-R2IN-Pad8)") (class "Default")
      (node (ref "U8") (pin "8") (pinfunction "R2IN_8") (pintype "passive"))
    )
    (net (code "112") (name "unconnected-(U8-R2OUT-Pad9)") (class "Default")
      (node (ref "U8") (pin "9") (pinfunction "R2OUT_9") (pintype "passive"))
    )
    (net (code "113") (name "unconnected-(U8-T2IN-Pad10)") (class "Default")
      (node (ref "U8") (pin "10") (pinfunction "T2IN_10") (pintype "passive"))
    )
    (net (code "114") (name "unconnected-(U8-T2OUT-Pad7)") (class "Default")
      (node (ref "U8") (pin "7") (pinfunction "T2OUT_7") (pintype "passive"))
    )
  )
)
